# 06-SX1276.net
KiCad netlist of a schematic drawn in Altium Designer
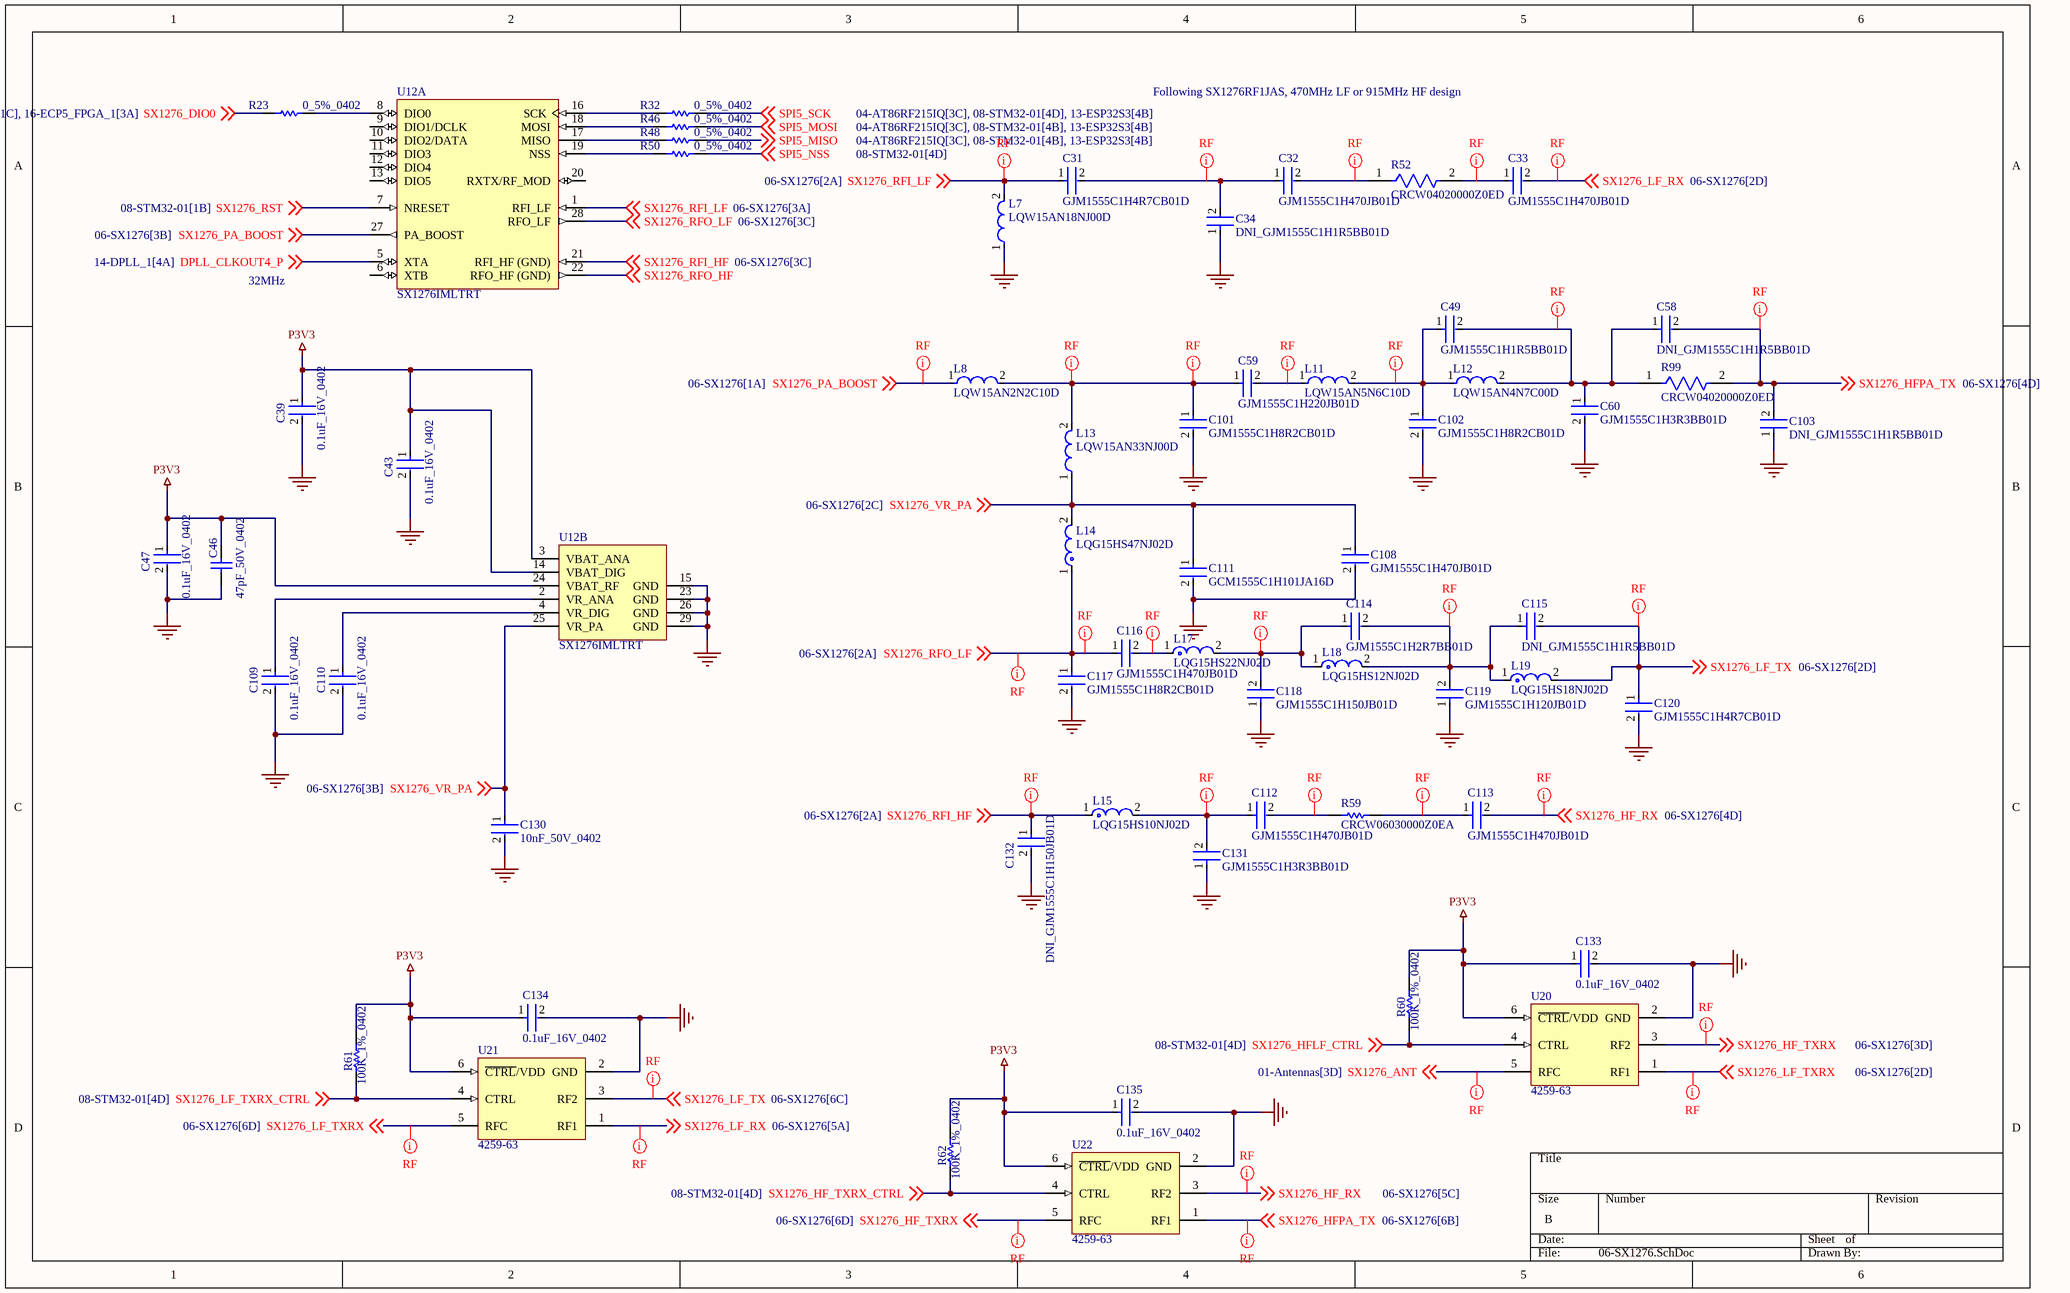
[diagram p0: 06-SX1276.SchDoc]

(export (version "E")
  (design (tool "Eeschema 10.0.6"))
  (components
    (comp (ref "C31")
      (value "GJM1555C1H4R7CB01D")
      (footprint "FP-GJM155-0_05-IPC_B")
      (description "Multi-Layer Ceramic Capacitor 4.7pF C0G  ±0.25pF 0402 Paper T/R")
      (fields (field (name "VOLTAGE") "50V"))
      (libsource (lib "Altium Content Vault") (part "02cd4be3c70576c341d710602a673aa"))
    )
    (comp (ref "C32")
      (value "GJM1555C1H470JB01D")
      (footprint "FP-GJM155-0_05-MFG")
      (description "Multi-Layer Ceramic Capacitor 47pF C0G  ±5% 0402 Paper T/R")
      (fields (field (name "TOLERANCE") "5%"))
      (libsource (lib "Altium Content Vault") (part "02cd4be3c70576c341d710602a673aa"))
    )
    (comp (ref "C33")
      (value "GJM1555C1H470JB01D")
      (footprint "FP-GJM155-0_05-MFG")
      (description "Multi-Layer Ceramic Capacitor 47pF C0G  ±5% 0402 Paper T/R")
      (fields (field (name "TOLERANCE") "5%"))
      (libsource (lib "Altium Content Vault") (part "02cd4be3c70576c341d710602a673aa"))
    )
    (comp (ref "C34")
      (value "DNI_GJM1555C1H1R5BB01D")
      (footprint "FP-GJM155-0_05-IPC_C")
      (description "Multi-Layer Ceramic Capacitor 1.5pF C0G  ±0.1pF 0402 Paper T/R")
      (fields (field (name "VOLTAGE") "50V"))
      (libsource (lib "Altium Content Vault") (part "02cd4be3c70576c341d710602a673aa"))
    )
    (comp (ref "C39")
      (value "0.1uF_16V_0402")
      (footprint "FP-C0402-BB-MFG")
      (description "CAP CER 0.1UF 16V 5% X7R 0402")
      (fields
        (field (name "MANUFACTURER") "Kemet")
        (field (name "MANUFACTURER PART NUMBER") "C0402C104J4RACTU")
      )
      (libsource (lib "Altium Content Vault") (part "b4654b650e69147ec39a6b967a45e02"))
    )
    (comp (ref "C43")
      (value "0.1uF_16V_0402")
      (footprint "FP-C0402-BB-MFG")
      (description "CAP CER 0.1UF 16V 5% X7R 0402")
      (fields
        (field (name "MANUFACTURER") "Kemet")
        (field (name "MANUFACTURER PART NUMBER") "C0402C104J4RACTU")
      )
      (libsource (lib "Altium Content Vault") (part "b4654b650e69147ec39a6b967a45e02"))
    )
    (comp (ref "C46")
      (value "47pF_50V_0402")
      (footprint "CAPC1005X55X25LL05T10")
      (fields (field (name "PART NUMBER") "GRM1555C1H470JA01D") (field (name "MANUFACTURER") "Murata"))
      (libsource (lib "Altium Content Vault") (part "CAP"))
    )
    (comp (ref "C47")
      (value "0.1uF_16V_0402")
      (footprint "FP-C0402-BB-MFG")
      (description "CAP CER 0.1UF 16V 5% X7R 0402")
      (fields
        (field (name "MANUFACTURER") "Kemet")
        (field (name "MANUFACTURER PART NUMBER") "C0402C104J4RACTU")
      )
      (libsource (lib "Altium Content Vault") (part "b4654b650e69147ec39a6b967a45e02"))
    )
    (comp (ref "C49")
      (value "GJM1555C1H1R5BB01D")
      (footprint "FP-GJM155-0_05-IPC_C")
      (description "Multi-Layer Ceramic Capacitor 1.5pF C0G  ±0.1pF 0402 Paper T/R")
      (fields (field (name "VOLTAGE") "50V"))
      (libsource (lib "Altium Content Vault") (part "02cd4be3c70576c341d710602a673aa"))
    )
    (comp (ref "C58")
      (value "DNI_GJM1555C1H1R5BB01D")
      (footprint "FP-GJM155-0_05-IPC_C")
      (description "Multi-Layer Ceramic Capacitor 1.5pF C0G  ±0.1pF 0402 Paper T/R")
      (fields (field (name "VOLTAGE") "50V"))
      (libsource (lib "Altium Content Vault") (part "02cd4be3c70576c341d710602a673aa"))
    )
    (comp (ref "C59")
      (value "GJM1555C1H220JB01D")
      (footprint "FP-GJM155-0_05-IPC_C")
      (description "Multi-Layer Ceramic Capacitor 22pF C0G  ±5% 0402 Paper T/R")
      (fields (field (name "TOLERANCE") "5%"))
      (libsource (lib "Altium Content Vault") (part "02cd4be3c70576c341d710602a673aa"))
    )
    (comp (ref "C60")
      (value "GJM1555C1H3R3BB01D")
      (footprint "FP-GJM155-0_05-IPC_C")
      (description "Multi-Layer Ceramic Capacitor 3.3pF C0G  ±0.1pF 0402 Paper T/R")
      (fields (field (name "VOLTAGE") "50V"))
      (libsource (lib "Altium Content Vault") (part "02cd4be3c70576c341d710602a673aa"))
    )
    (comp (ref "C101")
      (value "GJM1555C1H8R2CB01D")
      (footprint "FP-GJM155-0_05-IPC_C")
      (description "Multi-Layer Ceramic Capacitor 8.2pF C0G  ±0.25pF 0402 Paper T/R")
      (fields (field (name "VOLTAGE") "50V"))
      (libsource (lib "Altium Content Vault") (part "02cd4be3c70576c341d710602a673aa"))
    )
    (comp (ref "C102")
      (value "GJM1555C1H8R2CB01D")
      (footprint "FP-GJM155-0_05-IPC_C")
      (description "Multi-Layer Ceramic Capacitor 8.2pF C0G  ±0.25pF 0402 Paper T/R")
      (fields (field (name "VOLTAGE") "50V"))
      (libsource (lib "Altium Content Vault") (part "02cd4be3c70576c341d710602a673aa"))
    )
    (comp (ref "C103")
      (value "DNI_GJM1555C1H1R5BB01D")
      (footprint "FP-GJM155-0_05-IPC_C")
      (description "Multi-Layer Ceramic Capacitor 1.5pF C0G  ±0.1pF 0402 Paper T/R")
      (fields (field (name "VOLTAGE") "50V"))
      (libsource (lib "Altium Content Vault") (part "02cd4be3c70576c341d710602a673aa"))
    )
    (comp (ref "C108")
      (value "GJM1555C1H470JB01D")
      (footprint "FP-GJM155-0_05-MFG")
      (description "Multi-Layer Ceramic Capacitor 47pF C0G  ±5% 0402 Paper T/R")
      (fields (field (name "TOLERANCE") "5%"))
      (libsource (lib "Altium Content Vault") (part "02cd4be3c70576c341d710602a673aa"))
    )
    (comp (ref "C109")
      (value "0.1uF_16V_0402")
      (footprint "FP-C0402-BB-MFG")
      (description "CAP CER 0.1UF 16V 5% X7R 0402")
      (fields
        (field (name "MANUFACTURER") "Kemet")
        (field (name "MANUFACTURER PART NUMBER") "C0402C104J4RACTU")
      )
      (libsource (lib "Altium Content Vault") (part "b4654b650e69147ec39a6b967a45e02"))
    )
    (comp (ref "C110")
      (value "0.1uF_16V_0402")
      (footprint "FP-C0402-BB-MFG")
      (description "CAP CER 0.1UF 16V 5% X7R 0402")
      (fields
        (field (name "MANUFACTURER") "Kemet")
        (field (name "MANUFACTURER PART NUMBER") "C0402C104J4RACTU")
      )
      (libsource (lib "Altium Content Vault") (part "b4654b650e69147ec39a6b967a45e02"))
    )
    (comp (ref "C111")
      (value "GCM1555C1H101JA16D")
      (footprint "FP-GCM155-0_05-IPC_C")
      (description "Ceramic Capacitor for Automotive 100pF ±5% 50VDC C0G 0402 Paper T/R")
      (fields (field (name "VOLTAGE") "50V") (field (name "TOLERANCE") "5%"))
      (libsource (lib "Altium Content Vault") (part "02cd4be3c70576c341d710602a673aa"))
    )
    (comp (ref "C112")
      (value "GJM1555C1H470JB01D")
      (footprint "FP-GJM155-0_05-MFG")
      (description "Multi-Layer Ceramic Capacitor 47pF C0G  ±5% 0402 Paper T/R")
      (fields (field (name "TOLERANCE") "5%"))
      (libsource (lib "Altium Content Vault") (part "02cd4be3c70576c341d710602a673aa"))
    )
    (comp (ref "C113")
      (value "GJM1555C1H470JB01D")
      (footprint "FP-GJM155-0_05-MFG")
      (description "Multi-Layer Ceramic Capacitor 47pF C0G  ±5% 0402 Paper T/R")
      (fields (field (name "TOLERANCE") "5%"))
      (libsource (lib "Altium Content Vault") (part "02cd4be3c70576c341d710602a673aa"))
    )
    (comp (ref "C114")
      (value "GJM1555C1H2R7BB01D")
      (footprint "FP-GJM155-0_05-IPC_A")
      (description "Multi-Layer Ceramic Capacitor 2.7pF C0G  ±0.1pF 0402 Paper T/R")
      (fields (field (name "VOLTAGE") "50V"))
      (libsource (lib "Altium Content Vault") (part "02cd4be3c70576c341d710602a673aa"))
    )
    (comp (ref "C115")
      (value "DNI_GJM1555C1H1R5BB01D")
      (footprint "FP-GJM155-0_05-IPC_C")
      (description "Multi-Layer Ceramic Capacitor 1.5pF C0G  ±0.1pF 0402 Paper T/R")
      (fields (field (name "VOLTAGE") "50V"))
      (libsource (lib "Altium Content Vault") (part "02cd4be3c70576c341d710602a673aa"))
    )
    (comp (ref "C116")
      (value "GJM1555C1H470JB01D")
      (footprint "FP-GJM155-0_05-MFG")
      (description "Multi-Layer Ceramic Capacitor 47pF C0G  ±5% 0402 Paper T/R")
      (fields (field (name "TOLERANCE") "5%"))
      (libsource (lib "Altium Content Vault") (part "02cd4be3c70576c341d710602a673aa"))
    )
    (comp (ref "C117")
      (value "GJM1555C1H8R2CB01D")
      (footprint "FP-GJM155-0_05-IPC_C")
      (description "Multi-Layer Ceramic Capacitor 8.2pF C0G  ±0.25pF 0402 Paper T/R")
      (fields (field (name "VOLTAGE") "50V"))
      (libsource (lib "Altium Content Vault") (part "02cd4be3c70576c341d710602a673aa"))
    )
    (comp (ref "C118")
      (value "GJM1555C1H150JB01D")
      (footprint "FP-GJM155-0_05-IPC_A")
      (description "Multi-Layer Ceramic Capacitor 15pF C0G  ±5% 0402 Paper T/R")
      (fields (field (name "TOLERANCE") "5%") (field (name "VOLTAGE") "50V"))
      (libsource (lib "Altium Content Vault") (part "02cd4be3c70576c341d710602a673aa"))
    )
    (comp (ref "C119")
      (value "GJM1555C1H120JB01D")
      (footprint "FP-GJM155-0_05-IPC_A")
      (description "Multi-Layer Ceramic Capacitor 12pF C0G  ±5% 0402 Paper T/R")
      (fields (field (name "TOLERANCE") "5%") (field (name "VOLTAGE") "50V"))
      (libsource (lib "Altium Content Vault") (part "02cd4be3c70576c341d710602a673aa"))
    )
    (comp (ref "C120")
      (value "GJM1555C1H4R7CB01D")
      (footprint "FP-GJM155-0_05-IPC_B")
      (description "Multi-Layer Ceramic Capacitor 4.7pF C0G  ±0.25pF 0402 Paper T/R")
      (fields (field (name "VOLTAGE") "50V"))
      (libsource (lib "Altium Content Vault") (part "02cd4be3c70576c341d710602a673aa"))
    )
    (comp (ref "C130")
      (value "10nF_50V_0402")
      (footprint "FP-CL165-IPC_C")
      (description "Cap Ceramic 10nF 50V X7R ±10% SMD 0402 +125°C Paper T/R")
      (fields (field (name "VOLTAGE") "50V") (field (name "TOLERANCE") "10%"))
      (libsource (lib "Altium Content Vault") (part "b4654b650e69147ec39a6b967a45e02"))
    )
    (comp (ref "C131")
      (value "GJM1555C1H3R3BB01D")
      (footprint "FP-GJM155-0_05-IPC_C")
      (description "Multi-Layer Ceramic Capacitor 3.3pF C0G  ±0.1pF 0402 Paper T/R")
      (fields (field (name "VOLTAGE") "50V"))
      (libsource (lib "Altium Content Vault") (part "02cd4be3c70576c341d710602a673aa"))
    )
    (comp (ref "C132")
      (value "DNI_GJM1555C1H150JB01D")
      (footprint "FP-GJM155-0_05-IPC_A")
      (description "Multi-Layer Ceramic Capacitor 15pF C0G  ±5% 0402 Paper T/R")
      (fields (field (name "TOLERANCE") "5%") (field (name "VOLTAGE") "50V"))
      (libsource (lib "Altium Content Vault") (part "02cd4be3c70576c341d710602a673aa"))
    )
    (comp (ref "C133")
      (value "0.1uF_16V_0402")
      (footprint "FP-C0402-BB-MFG")
      (description "CAP CER 0.1UF 16V 5% X7R 0402")
      (fields
        (field (name "MANUFACTURER") "Kemet")
        (field (name "MANUFACTURER PART NUMBER") "C0402C104J4RACTU")
      )
      (libsource (lib "Altium Content Vault") (part "b4654b650e69147ec39a6b967a45e02"))
    )
    (comp (ref "C134")
      (value "0.1uF_16V_0402")
      (footprint "FP-C0402-BB-MFG")
      (description "CAP CER 0.1UF 16V 5% X7R 0402")
      (fields
        (field (name "MANUFACTURER") "Kemet")
        (field (name "MANUFACTURER PART NUMBER") "C0402C104J4RACTU")
      )
      (libsource (lib "Altium Content Vault") (part "b4654b650e69147ec39a6b967a45e02"))
    )
    (comp (ref "C135")
      (value "0.1uF_16V_0402")
      (footprint "FP-C0402-BB-MFG")
      (description "CAP CER 0.1UF 16V 5% X7R 0402")
      (fields
        (field (name "MANUFACTURER") "Kemet")
        (field (name "MANUFACTURER PART NUMBER") "C0402C104J4RACTU")
      )
      (libsource (lib "Altium Content Vault") (part "b4654b650e69147ec39a6b967a45e02"))
    )
    (comp (ref "L7")
      (value "LQW15AN18NJ00D")
      (footprint "FP-LQW15AN_00-W0_6-0_1-MFG")
      (description "Wire Wound RF Inductor 18nH ±5% 370mA 0.27Ω 0402 (1005)")
      (fields (field (name "TOLERANCE") "5%"))
      (libsource (lib "Altium Content Vault") (part "725321dda6339637d4d059423bc1c3c"))
    )
    (comp (ref "L8")
      (value "LQW15AN2N2C10D")
      (footprint "FP-LQW15AN_00-W0_6-0_1-MFG")
      (description "Wire Wound RF Inductor 2.2nH ±0.2nH 1000mA 0.027Ω 0402 (1005)")
      (libsource (lib "Altium Content Vault") (part "725321dda6339637d4d059423bc1c3c"))
    )
    (comp (ref "L11")
      (value "LQW15AN5N6C10D")
      (footprint "FP-LQW15AN_00-W0_6-0_1-MFG")
      (description "Wire Wound RF Inductor 5.6nH ±0.2nH 800mA 0.051Ω 0402 (1005)")
      (libsource (lib "Altium Content Vault") (part "725321dda6339637d4d059423bc1c3c"))
    )
    (comp (ref "L12")
      (value "LQW15AN4N7C00D")
      (footprint "FP-LQW15AN_00-W0_6-0_1-MFG")
      (description "Wire Wound RF Inductor 4.7nH ±0.2nH 750mA 0.07Ω 0402 (1005)")
      (libsource (lib "Altium Content Vault") (part "725321dda6339637d4d059423bc1c3c"))
    )
    (comp (ref "L13")
      (value "LQW15AN33NJ00D")
      (footprint "FP-LQW15AN_00-W0_5-0_1-MFG")
      (description "Wire Wound RF Inductor 33nH ±5% 260mA 0.63Ω 0402 (1005)")
      (fields (field (name "TOLERANCE") "5%"))
      (libsource (lib "Altium Content Vault") (part "725321dda6339637d4d059423bc1c3c"))
    )
    (comp (ref "L14")
      (value "LQG15HS47NJ02D")
      (footprint "FP-LQG15HH_02-IPC_B")
      (description "Multilayer type RF Inductor 47nH ±5% 0.72Ω 300mA 0402")
      (fields (field (name "TOLERANCE") "5%"))
      (libsource (lib "Altium Content Vault") (part "4cc4b267dca4c8e51f7102f422741d8"))
    )
    (comp (ref "L15")
      (value "LQG15HS10NJ02D")
      (footprint "FP-LQG15HH_02-IPC_A")
      (description "Multilayer type RF Inductor 10nH ±5% 0.26Ω 500mA 0402")
      (fields (field (name "TOLERANCE") "5%"))
      (libsource (lib "Altium Content Vault") (part "4cc4b267dca4c8e51f7102f422741d8"))
    )
    (comp (ref "L17")
      (value "LQG15HS22NJ02D")
      (footprint "FP-LQG15HH_02-MFG")
      (description "Multilayer type RF Inductor 22nH ±5% 0.42Ω 350mA 0402")
      (fields (field (name "TOLERANCE") "5%"))
      (libsource (lib "Altium Content Vault") (part "4cc4b267dca4c8e51f7102f422741d8"))
    )
    (comp (ref "L18")
      (value "LQG15HS12NJ02D")
      (footprint "FP-LQG15HH_02-IPC_A")
      (description "Multilayer type RF Inductor 12nH ±5% 0.28Ω 500mA 0402")
      (fields (field (name "TOLERANCE") "5%"))
      (libsource (lib "Altium Content Vault") (part "4cc4b267dca4c8e51f7102f422741d8"))
    )
    (comp (ref "L19")
      (value "LQG15HS18NJ02D")
      (footprint "FP-LQG15HH_02-MFG")
      (description "Multilayer type RF Inductor 18nH ±5% 0.36Ω 400mA 0402")
      (fields (field (name "TOLERANCE") "5%"))
      (libsource (lib "Altium Content Vault") (part "4cc4b267dca4c8e51f7102f422741d8"))
    )
    (comp (ref "R23")
      (value "0_5%_0402")
      (footprint "RESC1005X40X25NL05T10")
      (fields (field (name "MANUFACTURER") "Panasonic") (field (name "PART NUMBER") "ERJ-U020R00X"))
      (libsource (lib "Altium Content Vault") (part "RES"))
    )
    (comp (ref "R32")
      (value "0_5%_0402")
      (footprint "RESC1005X40X25NL05T10")
      (fields (field (name "MANUFACTURER") "Panasonic") (field (name "PART NUMBER") "ERJ-U020R00X"))
      (libsource (lib "Altium Content Vault") (part "RES"))
    )
    (comp (ref "R46")
      (value "0_5%_0402")
      (footprint "RESC1005X40X25NL05T10")
      (fields (field (name "MANUFACTURER") "Panasonic") (field (name "PART NUMBER") "ERJ-U020R00X"))
      (libsource (lib "Altium Content Vault") (part "RES"))
    )
    (comp (ref "R48")
      (value "0_5%_0402")
      (footprint "RESC1005X40X25NL05T10")
      (fields (field (name "MANUFACTURER") "Panasonic") (field (name "PART NUMBER") "ERJ-U020R00X"))
      (libsource (lib "Altium Content Vault") (part "RES"))
    )
    (comp (ref "R50")
      (value "0_5%_0402")
      (footprint "RESC1005X40X25NL05T10")
      (fields (field (name "MANUFACTURER") "Panasonic") (field (name "PART NUMBER") "ERJ-U020R00X"))
      (libsource (lib "Altium Content Vault") (part "RES"))
    )
    (comp (ref "R52")
      (value "CRCW04020000Z0ED")
      (footprint "FP-CRCW0402-e3-IPC_C")
      (description "RES Thick Film, 0Ω, 0.063W, 0402")
      (fields (field (name "TOLERANCE") "5%"))
      (libsource (lib "Altium Content Vault") (part "1029c3af85768c4190bb7ad29bc67b5"))
    )
    (comp (ref "R59")
      (value "CRCW06030000Z0EA")
      (footprint "RESC1609X50X30NL8T20")
      (description "Chip Resistor, 0 Ohm, Jumper, 100 mW, -55 to 155 degC, 0603 (1608 Metric), RoHS, Tape and Reel")
      (fields (field (name "MANUFACTURER") "Vishay Semiconductor"))
      (libsource (lib "Altium Content Vault") (part "RES-2"))
    )
    (comp (ref "R60")
      (value "100K_1%_0402")
      (footprint "RESC1005X40X25ML05T10")
      (fields (field (name "MANUFACTURER") "Yageo") (field (name "PART NUMBER") "RC0402FR-13100KL"))
      (libsource (lib "Altium Content Vault") (part "RES"))
    )
    (comp (ref "R61")
      (value "100K_1%_0402")
      (footprint "RESC1005X40X25ML05T10")
      (fields (field (name "MANUFACTURER") "Yageo") (field (name "PART NUMBER") "RC0402FR-13100KL"))
      (libsource (lib "Altium Content Vault") (part "RES"))
    )
    (comp (ref "R62")
      (value "100K_1%_0402")
      (footprint "RESC1005X40X25ML05T10")
      (fields (field (name "MANUFACTURER") "Yageo") (field (name "PART NUMBER") "RC0402FR-13100KL"))
      (libsource (lib "Altium Content Vault") (part "RES"))
    )
    (comp (ref "R99")
      (value "CRCW04020000Z0ED")
      (footprint "FP-CRCW0402-e3-IPC_C")
      (description "RES Thick Film, 0Ω, 0.063W, 0402")
      (fields (field (name "TOLERANCE") "5%"))
      (libsource (lib "Altium Content Vault") (part "1029c3af85768c4190bb7ad29bc67b5"))
    )
    (comp (ref "U12")
      (value "SX1276IMLTRT")
      (footprint "SMTC-QFN-28_V")
      (description "Low Power Long Range Transceiver, 137 to 1020 MHz, -40 to 85 degC, 28-Pin QFN, RoHS, Tape and Reel")
      (fields (field (name "MANUFACTURER") "Semtech"))
      (libsource (lib "Altium Content Vault") (part "SMTC-SX127X-QFN-28"))
    )
    (comp (ref "U20")
      (value "4259-63")
      (footprint "PERE-SC-70-6_M")
      (description "IC RF Switch SPDT, 50 Ohm, 6-Pin SC70, RoHS, Tape and Reel")
      (fields (field (name "MANUFACTURER") "Peregrine Semiconductor"))
      (libsource (lib "Altium Content Vault") (part "PERE-PE4259-6"))
    )
    (comp (ref "U21")
      (value "4259-63")
      (footprint "PERE-SC-70-6_M")
      (description "IC RF Switch SPDT, 50 Ohm, 6-Pin SC70, RoHS, Tape and Reel")
      (fields (field (name "MANUFACTURER") "Peregrine Semiconductor"))
      (libsource (lib "Altium Content Vault") (part "PERE-PE4259-6"))
    )
    (comp (ref "U22")
      (value "4259-63")
      (footprint "PERE-SC-70-6_M")
      (description "IC RF Switch SPDT, 50 Ohm, 6-Pin SC70, RoHS, Tape and Reel")
      (fields (field (name "MANUFACTURER") "Peregrine Semiconductor"))
      (libsource (lib "Altium Content Vault") (part "PERE-PE4259-6"))
    )
  )
  (nets
    (net (code "1") (name "DPLL_CLKOUT4_P") (class "Default")
      (node (ref "U12") (pin "5") (pinfunction "XTA_5") (pintype "bidirectional"))
    )
    (net (code "2") (name "GND") (class "Default")
      (node (ref "C101") (pin "2") (pinfunction "2_2") (pintype "passive"))
      (node (ref "C102") (pin "2") (pinfunction "2_2") (pintype "passive"))
      (node (ref "C103") (pin "1") (pinfunction "1_1") (pintype "passive"))
      (node (ref "C108") (pin "2") (pinfunction "2_2") (pintype "passive"))
      (node (ref "C109") (pin "2") (pinfunction "2_2") (pintype "passive"))
      (node (ref "C110") (pin "2") (pinfunction "2_2") (pintype "passive"))
      (node (ref "C111") (pin "2") (pinfunction "2_2") (pintype "passive"))
      (node (ref "C117") (pin "2") (pinfunction "2_2") (pintype "passive"))
      (node (ref "C118") (pin "1") (pinfunction "1_1") (pintype "passive"))
      (node (ref "C119") (pin "1") (pinfunction "1_1") (pintype "passive"))
      (node (ref "C120") (pin "2") (pinfunction "2_2") (pintype "passive"))
      (node (ref "C130") (pin "2") (pinfunction "2_2") (pintype "passive"))
      (node (ref "C131") (pin "1") (pinfunction "1_1") (pintype "passive"))
      (node (ref "C132") (pin "2") (pinfunction "2_2") (pintype "passive"))
      (node (ref "C133") (pin "2") (pinfunction "2_2") (pintype "passive"))
      (node (ref "C134") (pin "2") (pinfunction "2_2") (pintype "passive"))
      (node (ref "C135") (pin "2") (pinfunction "2_2") (pintype "passive"))
      (node (ref "C34") (pin "1") (pinfunction "1_1") (pintype "passive"))
      (node (ref "C39") (pin "2") (pinfunction "2_2") (pintype "passive"))
      (node (ref "C43") (pin "2") (pinfunction "2_2") (pintype "passive"))
      (node (ref "C46") (pin "1") (pinfunction "1_1") (pintype "passive"))
      (node (ref "C47") (pin "2") (pinfunction "2_2") (pintype "passive"))
      (node (ref "C60") (pin "2") (pinfunction "2_2") (pintype "passive"))
      (node (ref "L7") (pin "1") (pinfunction "1_1") (pintype "passive"))
      (node (ref "U12") (pin "15") (pinfunction "GND_15") (pintype "power_in"))
      (node (ref "U12") (pin "23") (pinfunction "GND_23") (pintype "power_in"))
      (node (ref "U12") (pin "26") (pinfunction "GND_26") (pintype "power_in"))
      (node (ref "U12") (pin "29") (pinfunction "GND_29") (pintype "power_in"))
      (node (ref "U20") (pin "2") (pinfunction "GND_2") (pintype "power_in"))
      (node (ref "U21") (pin "2") (pinfunction "GND_2") (pintype "power_in"))
      (node (ref "U22") (pin "2") (pinfunction "GND_2") (pintype "power_in"))
    )
    (net (code "3") (name "Net-(C31-Pad2)") (class "Default")
      (node (ref "C31") (pin "2") (pinfunction "2_2") (pintype "passive"))
      (node (ref "C32") (pin "1") (pinfunction "1_1") (pintype "passive"))
      (node (ref "C34") (pin "2") (pinfunction "2_2") (pintype "passive"))
    )
    (net (code "4") (name "Net-(C32-Pad2)") (class "Default")
      (node (ref "C32") (pin "2") (pinfunction "2_2") (pintype "passive"))
      (node (ref "R52") (pin "1") (pinfunction "1_1") (pintype "passive"))
    )
    (net (code "5") (name "Net-(C33-Pad1)") (class "Default")
      (node (ref "C33") (pin "1") (pinfunction "1_1") (pintype "passive"))
      (node (ref "R52") (pin "2") (pinfunction "2_2") (pintype "passive"))
    )
    (net (code "6") (name "Net-(C49-Pad2)") (class "Default")
      (node (ref "C49") (pin "2") (pinfunction "2_2") (pintype "passive"))
      (node (ref "C58") (pin "1") (pinfunction "1_1") (pintype "passive"))
      (node (ref "C60") (pin "1") (pinfunction "1_1") (pintype "passive"))
      (node (ref "L12") (pin "2") (pinfunction "2_2") (pintype "passive"))
      (node (ref "R99") (pin "1") (pinfunction "1_1") (pintype "passive"))
    )
    (net (code "7") (name "Net-(C59-Pad2)") (class "Default")
      (node (ref "C59") (pin "2") (pinfunction "2_2") (pintype "passive"))
      (node (ref "L11") (pin "1") (pinfunction "1_1") (pintype "passive"))
    )
    (net (code "8") (name "Net-(C101-Pad1)") (class "Default")
      (node (ref "C101") (pin "1") (pinfunction "1_1") (pintype "passive"))
      (node (ref "C59") (pin "1") (pinfunction "1_1") (pintype "passive"))
      (node (ref "L13") (pin "2") (pinfunction "2_2") (pintype "passive"))
      (node (ref "L8") (pin "2") (pinfunction "2_2") (pintype "passive"))
    )
    (net (code "9") (name "Net-(C102-Pad1)") (class "Default")
      (node (ref "C102") (pin "1") (pinfunction "1_1") (pintype "passive"))
      (node (ref "C49") (pin "1") (pinfunction "1_1") (pintype "passive"))
      (node (ref "L11") (pin "2") (pinfunction "2_2") (pintype "passive"))
      (node (ref "L12") (pin "1") (pinfunction "1_1") (pintype "passive"))
    )
    (net (code "10") (name "Net-(C112-Pad1)") (class "Default")
      (node (ref "C112") (pin "1") (pinfunction "1_1") (pintype "passive"))
      (node (ref "C131") (pin "2") (pinfunction "2_2") (pintype "passive"))
      (node (ref "L15") (pin "2") (pinfunction "2_2") (pintype "passive"))
    )
    (net (code "11") (name "Net-(C112-Pad2)") (class "Default")
      (node (ref "C112") (pin "2") (pinfunction "2_2") (pintype "passive"))
      (node (ref "R59") (pin "1") (pinfunction "1_1") (pintype "passive"))
    )
    (net (code "12") (name "Net-(C113-Pad1)") (class "Default")
      (node (ref "C113") (pin "1") (pinfunction "1_1") (pintype "passive"))
      (node (ref "R59") (pin "2") (pinfunction "2_2") (pintype "passive"))
    )
    (net (code "13") (name "Net-(C114-Pad1)") (class "Default")
      (node (ref "C114") (pin "1") (pinfunction "1_1") (pintype "passive"))
      (node (ref "C118") (pin "2") (pinfunction "2_2") (pintype "passive"))
      (node (ref "L17") (pin "2") (pinfunction "2_2") (pintype "passive"))
      (node (ref "L18") (pin "1") (pinfunction "1_1") (pintype "passive"))
    )
    (net (code "14") (name "Net-(C114-Pad2)") (class "Default")
      (node (ref "C114") (pin "2") (pinfunction "2_2") (pintype "passive"))
      (node (ref "C115") (pin "1") (pinfunction "1_1") (pintype "passive"))
      (node (ref "C119") (pin "2") (pinfunction "2_2") (pintype "passive"))
      (node (ref "L18") (pin "2") (pinfunction "2_2") (pintype "passive"))
      (node (ref "L19") (pin "1") (pinfunction "1_1") (pintype "passive"))
    )
    (net (code "15") (name "Net-(C116-Pad2)") (class "Default")
      (node (ref "C116") (pin "2") (pinfunction "2_2") (pintype "passive"))
      (node (ref "L17") (pin "1") (pinfunction "1_1") (pintype "passive"))
    )
    (net (code "16") (name "Net-(U12A-DIO0)") (class "Default")
      (node (ref "R23") (pin "2") (pinfunction "2_2") (pintype "passive"))
      (node (ref "U12") (pin "8") (pinfunction "DIO0_8") (pintype "bidirectional"))
    )
    (net (code "17") (name "Net-(U12A-MISO)") (class "Default")
      (node (ref "R48") (pin "1") (pinfunction "1_1") (pintype "passive"))
      (node (ref "U12") (pin "17") (pinfunction "MISO_17") (pintype "tri_state"))
    )
    (net (code "18") (name "Net-(U12A-MOSI)") (class "Default")
      (node (ref "R46") (pin "1") (pinfunction "1_1") (pintype "passive"))
      (node (ref "U12") (pin "18") (pinfunction "MOSI_18") (pintype "input"))
    )
    (net (code "19") (name "Net-(U12A-NSS)") (class "Default")
      (node (ref "R50") (pin "1") (pinfunction "1_1") (pintype "passive"))
      (node (ref "U12") (pin "19") (pinfunction "NSS_19") (pintype "input"))
    )
    (net (code "20") (name "Net-(U12A-SCK)") (class "Default")
      (node (ref "R32") (pin "1") (pinfunction "1_1") (pintype "passive"))
      (node (ref "U12") (pin "16") (pinfunction "SCK_16") (pintype "input"))
    )
    (net (code "21") (name "Net-(U12B-VR_ANA)") (class "Default")
      (node (ref "C109") (pin "1") (pinfunction "1_1") (pintype "passive"))
      (node (ref "U12") (pin "2") (pinfunction "VR_ANA_2") (pintype "power_in"))
    )
    (net (code "22") (name "Net-(U12B-VR_DIG)") (class "Default")
      (node (ref "C110") (pin "1") (pinfunction "1_1") (pintype "passive"))
      (node (ref "U12") (pin "4") (pinfunction "VR_DIG_4") (pintype "power_in"))
    )
    (net (code "23") (name "P3V3") (class "Default")
      (node (ref "C133") (pin "1") (pinfunction "1_1") (pintype "passive"))
      (node (ref "C134") (pin "1") (pinfunction "1_1") (pintype "passive"))
      (node (ref "C135") (pin "1") (pinfunction "1_1") (pintype "passive"))
      (node (ref "C39") (pin "1") (pinfunction "1_1") (pintype "passive"))
      (node (ref "C43") (pin "1") (pinfunction "1_1") (pintype "passive"))
      (node (ref "C46") (pin "2") (pinfunction "2_2") (pintype "passive"))
      (node (ref "C47") (pin "1") (pinfunction "1_1") (pintype "passive"))
      (node (ref "R60") (pin "2") (pinfunction "2_2") (pintype "passive"))
      (node (ref "R61") (pin "2") (pinfunction "2_2") (pintype "passive"))
      (node (ref "R62") (pin "2") (pinfunction "2_2") (pintype "passive"))
      (node (ref "U12") (pin "14") (pinfunction "VBAT_DIG_14") (pintype "power_in"))
      (node (ref "U12") (pin "24") (pinfunction "VBAT_RF_24") (pintype "power_in"))
      (node (ref "U12") (pin "3") (pinfunction "VBAT_ANA_3") (pintype "power_in"))
      (node (ref "U20") (pin "6") (pinfunction "~{CTRL}/VDD_6") (pintype "input"))
      (node (ref "U21") (pin "6") (pinfunction "~{CTRL}/VDD_6") (pintype "input"))
      (node (ref "U22") (pin "6") (pinfunction "~{CTRL}/VDD_6") (pintype "input"))
    )
    (net (code "24") (name "SPI5_MISO") (class "Default")
      (node (ref "R48") (pin "2") (pinfunction "2_2") (pintype "passive"))
    )
    (net (code "25") (name "SPI5_MOSI") (class "Default")
      (node (ref "R46") (pin "2") (pinfunction "2_2") (pintype "passive"))
    )
    (net (code "26") (name "SPI5_NSS") (class "Default")
      (node (ref "R50") (pin "2") (pinfunction "2_2") (pintype "passive"))
    )
    (net (code "27") (name "SPI5_SCK") (class "Default")
      (node (ref "R32") (pin "2") (pinfunction "2_2") (pintype "passive"))
    )
    (net (code "28") (name "SX1276_ANT") (class "Default")
      (node (ref "U20") (pin "5") (pinfunction "RFC_5") (pintype "passive"))
    )
    (net (code "29") (name "SX1276_DIO0") (class "Default")
      (node (ref "R23") (pin "1") (pinfunction "1_1") (pintype "passive"))
    )
    (net (code "30") (name "SX1276_HFLF_CTRL") (class "Default")
      (node (ref "R60") (pin "1") (pinfunction "1_1") (pintype "passive"))
      (node (ref "U20") (pin "4") (pinfunction "CTRL_4") (pintype "input"))
    )
    (net (code "31") (name "SX1276_HFPA_TX") (class "Default")
      (node (ref "C103") (pin "2") (pinfunction "2_2") (pintype "passive"))
      (node (ref "C58") (pin "2") (pinfunction "2_2") (pintype "passive"))
      (node (ref "R99") (pin "2") (pinfunction "2_2") (pintype "passive"))
      (node (ref "U22") (pin "1") (pinfunction "RF1_1") (pintype "passive"))
    )
    (net (code "32") (name "SX1276_HF_RX") (class "Default")
      (node (ref "C113") (pin "2") (pinfunction "2_2") (pintype "passive"))
      (node (ref "U22") (pin "3") (pinfunction "RF2_3") (pintype "passive"))
    )
    (net (code "33") (name "SX1276_HF_TXRX") (class "Default")
      (node (ref "U20") (pin "3") (pinfunction "RF2_3") (pintype "passive"))
      (node (ref "U22") (pin "5") (pinfunction "RFC_5") (pintype "passive"))
    )
    (net (code "34") (name "SX1276_HF_TXRX_CTRL") (class "Default")
      (node (ref "R62") (pin "1") (pinfunction "1_1") (pintype "passive"))
      (node (ref "U22") (pin "4") (pinfunction "CTRL_4") (pintype "input"))
    )
    (net (code "35") (name "SX1276_LF_RX") (class "Default")
      (node (ref "C33") (pin "2") (pinfunction "2_2") (pintype "passive"))
      (node (ref "U21") (pin "1") (pinfunction "RF1_1") (pintype "passive"))
    )
    (net (code "36") (name "SX1276_LF_TX") (class "Default")
      (node (ref "C115") (pin "2") (pinfunction "2_2") (pintype "passive"))
      (node (ref "C120") (pin "1") (pinfunction "1_1") (pintype "passive"))
      (node (ref "L19") (pin "2") (pinfunction "2_2") (pintype "passive"))
      (node (ref "U21") (pin "3") (pinfunction "RF2_3") (pintype "passive"))
    )
    (net (code "37") (name "SX1276_LF_TXRX") (class "Default")
      (node (ref "U20") (pin "1") (pinfunction "RF1_1") (pintype "passive"))
      (node (ref "U21") (pin "5") (pinfunction "RFC_5") (pintype "passive"))
    )
    (net (code "38") (name "SX1276_LF_TXRX_CTRL") (class "Default")
      (node (ref "R61") (pin "1") (pinfunction "1_1") (pintype "passive"))
      (node (ref "U21") (pin "4") (pinfunction "CTRL_4") (pintype "input"))
    )
    (net (code "39") (name "SX1276_PA_BOOST") (class "Default")
      (node (ref "L8") (pin "1") (pinfunction "1_1") (pintype "passive"))
      (node (ref "U12") (pin "27") (pinfunction "PA_BOOST_27") (pintype "output"))
    )
    (net (code "40") (name "SX1276_RFI_HF") (class "Default")
      (node (ref "C132") (pin "1") (pinfunction "1_1") (pintype "passive"))
      (node (ref "L15") (pin "1") (pinfunction "1_1") (pintype "passive"))
      (node (ref "U12") (pin "21") (pinfunction "RFI_HF_(GND)_21") (pintype "input"))
    )
    (net (code "41") (name "SX1276_RFI_LF") (class "Default")
      (node (ref "C31") (pin "1") (pinfunction "1_1") (pintype "passive"))
      (node (ref "L7") (pin "2") (pinfunction "2_2") (pintype "passive"))
      (node (ref "U12") (pin "1") (pinfunction "RFI_LF_1") (pintype "input"))
    )
    (net (code "42") (name "SX1276_RFO_HF") (class "Default")
      (node (ref "U12") (pin "22") (pinfunction "RFO_HF_(GND)_22") (pintype "output"))
    )
    (net (code "43") (name "SX1276_RFO_LF") (class "Default")
      (node (ref "C116") (pin "1") (pinfunction "1_1") (pintype "passive"))
      (node (ref "C117") (pin "1") (pinfunction "1_1") (pintype "passive"))
      (node (ref "L14") (pin "1") (pinfunction "1_1") (pintype "passive"))
      (node (ref "U12") (pin "28") (pinfunction "RFO_LF_28") (pintype "output"))
    )
    (net (code "44") (name "SX1276_RST") (class "Default")
      (node (ref "U12") (pin "7") (pinfunction "NRESET_7") (pintype "input"))
    )
    (net (code "45") (name "SX1276_VR_PA") (class "Default")
      (node (ref "C108") (pin "1") (pinfunction "1_1") (pintype "passive"))
      (node (ref "C111") (pin "1") (pinfunction "1_1") (pintype "passive"))
      (node (ref "C130") (pin "1") (pinfunction "1_1") (pintype "passive"))
      (node (ref "L13") (pin "1") (pinfunction "1_1") (pintype "passive"))
      (node (ref "L14") (pin "2") (pinfunction "2_2") (pintype "passive"))
      (node (ref "U12") (pin "25") (pinfunction "VR_PA_25") (pintype "power_in"))
    )
    (net (code "46") (name "unconnected-(U12A-DIO1{slash}DCLK-Pad9)") (class "Default")
      (node (ref "U12") (pin "9") (pinfunction "DIO1/DCLK_9") (pintype "bidirectional"))
    )
    (net (code "47") (name "unconnected-(U12A-DIO2{slash}DATA-Pad10)") (class "Default")
      (node (ref "U12") (pin "10") (pinfunction "DIO2/DATA_10") (pintype "bidirectional"))
    )
    (net (code "48") (name "unconnected-(U12A-DIO3-Pad11)") (class "Default")
      (node (ref "U12") (pin "11") (pinfunction "DIO3_11") (pintype "bidirectional"))
    )
    (net (code "49") (name "unconnected-(U12A-DIO4-Pad12)") (class "Default")
      (node (ref "U12") (pin "12") (pinfunction "DIO4_12") (pintype "bidirectional"))
    )
    (net (code "50") (name "unconnected-(U12A-DIO5-Pad13)") (class "Default")
      (node (ref "U12") (pin "13") (pinfunction "DIO5_13") (pintype "bidirectional"))
    )
    (net (code "51") (name "unconnected-(U12A-RXTX{slash}RF_MOD-Pad20)") (class "Default")
      (node (ref "U12") (pin "20") (pinfunction "RXTX/RF_MOD_20") (pintype "bidirectional"))
    )
    (net (code "52") (name "unconnected-(U12A-XTB-Pad6)") (class "Default")
      (node (ref "U12") (pin "6") (pinfunction "XTB_6") (pintype "bidirectional"))
    )
  )
)
